# bekono_mini.net
KiCad netlist of a schematic drawn in EAGLE
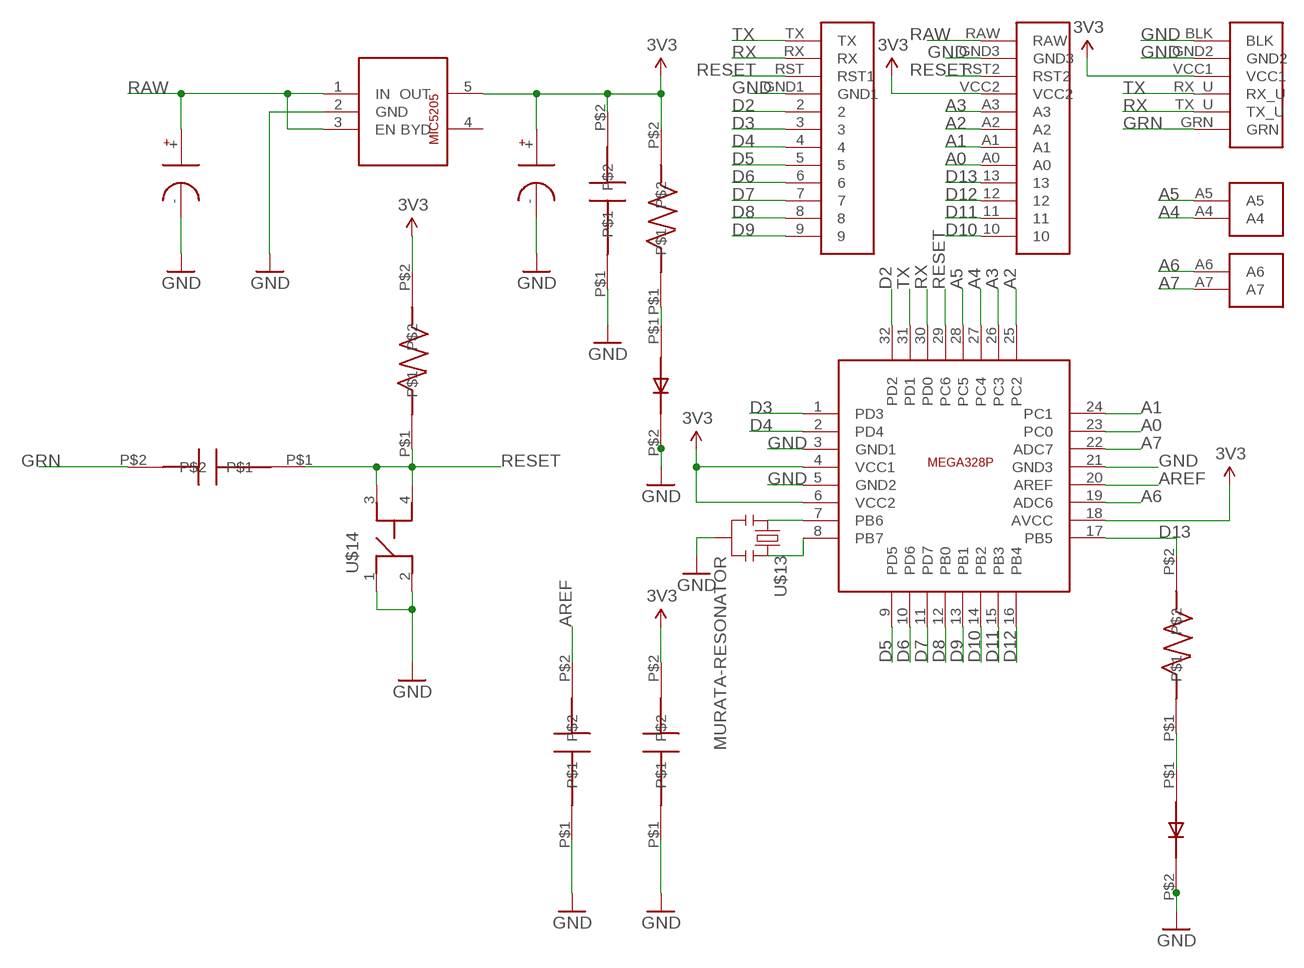
[diagram p0: schematic, sheet 1]

(export (version "E")
  (design (tool "Eeschema 10.0.6"))
  (components
    (comp (ref "U$1")
      (value "ARDUIN-MINIPRO-BASE")
      (footprint "eagle-import:ARDUINO-MINIPRO-BASE")
      (libsource (lib "eagle-import") (part "ARDUIN-MINIPRO-BASE"))
    )
    (comp (ref "U$2")
      (value "MICREL-MIC5205")
      (footprint "eagle-import:MICREL-MIC5205")
      (libsource (lib "eagle-import") (part "MICREL-MIC5205"))
    )
    (comp (ref "U$3")
      (value "TANTALUM-CAPACITOR-1206")
      (footprint "eagle-import:TANTALUM-CAPACITOR-1206")
      (libsource (lib "eagle-import") (part "TANTALUM-CAPACITOR-1206"))
    )
    (comp (ref "U$4")
      (value "TANTALUM-CAPACITOR-1206")
      (footprint "eagle-import:TANTALUM-CAPACITOR-1206")
      (libsource (lib "eagle-import") (part "TANTALUM-CAPACITOR-1206"))
    )
    (comp (ref "U$5")
      (value "CAPACITOR-0603")
      (footprint "eagle-import:0603")
      (libsource (lib "eagle-import") (part "CAPACITOR-0603"))
    )
    (comp (ref "U$6")
      (value "RESISTOR-0603")
      (footprint "eagle-import:0603")
      (libsource (lib "eagle-import") (part "RESISTOR-0603"))
    )
    (comp (ref "U$7")
      (value "LED-0603")
      (footprint "eagle-import:0603")
      (libsource (lib "eagle-import") (part "LED-0603"))
    )
    (comp (ref "U$8")
      (value "ATMEL-MEGA328P")
      (footprint "eagle-import:ATNEL-MEGA328P")
      (libsource (lib "eagle-import") (part "ATMEL-MEGA328P"))
    )
    (comp (ref "U$9")
      (value "RESISTOR-0603")
      (footprint "eagle-import:0603")
      (libsource (lib "eagle-import") (part "RESISTOR-0603"))
    )
    (comp (ref "U$10")
      (value "LED-0603")
      (footprint "eagle-import:0603")
      (libsource (lib "eagle-import") (part "LED-0603"))
    )
    (comp (ref "U$11")
      (value "CAPACITOR-0603")
      (footprint "eagle-import:0603")
      (libsource (lib "eagle-import") (part "CAPACITOR-0603"))
    )
    (comp (ref "U$12")
      (value "CAPACITOR-0603")
      (footprint "eagle-import:0603")
      (libsource (lib "eagle-import") (part "CAPACITOR-0603"))
    )
    (comp (ref "U$13")
      (value "MURATA-RESONATOR")
      (footprint "eagle-import:MURATA-RESONATOR")
      (libsource (lib "eagle-import") (part "MURATA-RESONATOR"))
    )
    (comp (ref "U$14")
      (value "SWITCH-LS6J2M-T")
      (footprint "eagle-import:SWITCH-LS6J2M-T")
      (libsource (lib "eagle-import") (part "SWITCH-LS6J2M-T"))
    )
    (comp (ref "U$15")
      (value "RESISTOR-0603")
      (footprint "eagle-import:0603")
      (libsource (lib "eagle-import") (part "RESISTOR-0603"))
    )
    (comp (ref "U$16")
      (value "CAPACITOR-0603")
      (footprint "eagle-import:0603")
      (libsource (lib "eagle-import") (part "CAPACITOR-0603"))
    )
  )
  (nets
    (net (code "1") (name "/A0") (class "Default")
      (node (ref "U$1") (pin "A0") (pinfunction "A0_A0") (pintype "bidirectional"))
      (node (ref "U$8") (pin "23") (pinfunction "PC0_23") (pintype "bidirectional"))
    )
    (net (code "2") (name "/A1") (class "Default")
      (node (ref "U$1") (pin "A1") (pinfunction "A1_A1") (pintype "bidirectional"))
      (node (ref "U$8") (pin "24") (pinfunction "PC1_24") (pintype "bidirectional"))
    )
    (net (code "3") (name "/A2") (class "Default")
      (node (ref "U$1") (pin "A2") (pinfunction "A2_A2") (pintype "bidirectional"))
      (node (ref "U$8") (pin "25") (pinfunction "PC2_25") (pintype "bidirectional"))
    )
    (net (code "4") (name "/A3") (class "Default")
      (node (ref "U$1") (pin "A3") (pinfunction "A3_A3") (pintype "bidirectional"))
      (node (ref "U$8") (pin "26") (pinfunction "PC3_26") (pintype "bidirectional"))
    )
    (net (code "5") (name "/A4") (class "Default")
      (node (ref "U$1") (pin "A4") (pinfunction "A4_A4") (pintype "bidirectional"))
      (node (ref "U$8") (pin "27") (pinfunction "PC4_27") (pintype "bidirectional"))
    )
    (net (code "6") (name "/A5") (class "Default")
      (node (ref "U$1") (pin "A5") (pinfunction "A5_A5") (pintype "bidirectional"))
      (node (ref "U$8") (pin "28") (pinfunction "PC5_28") (pintype "bidirectional"))
    )
    (net (code "7") (name "/A6") (class "Default")
      (node (ref "U$1") (pin "A6") (pinfunction "A6_A6") (pintype "bidirectional"))
      (node (ref "U$8") (pin "19") (pinfunction "ADC6_19") (pintype "bidirectional"))
    )
    (net (code "8") (name "/A7") (class "Default")
      (node (ref "U$1") (pin "A7") (pinfunction "A7_A7") (pintype "bidirectional"))
      (node (ref "U$8") (pin "22") (pinfunction "ADC7_22") (pintype "bidirectional"))
    )
    (net (code "9") (name "/AREF") (class "Default")
      (node (ref "U$12") (pin "P$2") (pinfunction "P$2_P$2") (pintype "bidirectional"))
      (node (ref "U$8") (pin "20") (pinfunction "AREF_20") (pintype "bidirectional"))
    )
    (net (code "10") (name "/D2") (class "Default")
      (node (ref "U$1") (pin "2") (pinfunction "2_2") (pintype "bidirectional"))
      (node (ref "U$8") (pin "32") (pinfunction "PD2_32") (pintype "bidirectional"))
    )
    (net (code "11") (name "/D3") (class "Default")
      (node (ref "U$1") (pin "3") (pinfunction "3_3") (pintype "bidirectional"))
      (node (ref "U$8") (pin "1") (pinfunction "PD3_1") (pintype "bidirectional"))
    )
    (net (code "12") (name "/D4") (class "Default")
      (node (ref "U$1") (pin "4") (pinfunction "4_4") (pintype "bidirectional"))
      (node (ref "U$8") (pin "2") (pinfunction "PD4_2") (pintype "bidirectional"))
    )
    (net (code "13") (name "/D5") (class "Default")
      (node (ref "U$1") (pin "5") (pinfunction "5_5") (pintype "bidirectional"))
      (node (ref "U$8") (pin "9") (pinfunction "PD5_9") (pintype "bidirectional"))
    )
    (net (code "14") (name "/D6") (class "Default")
      (node (ref "U$1") (pin "6") (pinfunction "6_6") (pintype "bidirectional"))
      (node (ref "U$8") (pin "10") (pinfunction "PD6_10") (pintype "bidirectional"))
    )
    (net (code "15") (name "/D7") (class "Default")
      (node (ref "U$1") (pin "7") (pinfunction "7_7") (pintype "bidirectional"))
      (node (ref "U$8") (pin "11") (pinfunction "PD7_11") (pintype "bidirectional"))
    )
    (net (code "16") (name "/D8") (class "Default")
      (node (ref "U$1") (pin "8") (pinfunction "8_8") (pintype "bidirectional"))
      (node (ref "U$8") (pin "12") (pinfunction "PB0_12") (pintype "bidirectional"))
    )
    (net (code "17") (name "/D9") (class "Default")
      (node (ref "U$1") (pin "9") (pinfunction "9_9") (pintype "bidirectional"))
      (node (ref "U$8") (pin "13") (pinfunction "PB1_13") (pintype "bidirectional"))
    )
    (net (code "18") (name "/D10") (class "Default")
      (node (ref "U$1") (pin "10") (pinfunction "10_10") (pintype "bidirectional"))
      (node (ref "U$8") (pin "14") (pinfunction "PB2_14") (pintype "bidirectional"))
    )
    (net (code "19") (name "/D11") (class "Default")
      (node (ref "U$1") (pin "11") (pinfunction "11_11") (pintype "bidirectional"))
      (node (ref "U$8") (pin "15") (pinfunction "PB3_15") (pintype "bidirectional"))
    )
    (net (code "20") (name "/D12") (class "Default")
      (node (ref "U$1") (pin "12") (pinfunction "12_12") (pintype "bidirectional"))
      (node (ref "U$8") (pin "16") (pinfunction "PB4_16") (pintype "bidirectional"))
    )
    (net (code "21") (name "/D13") (class "Default")
      (node (ref "U$1") (pin "13") (pinfunction "13_13") (pintype "bidirectional"))
      (node (ref "U$8") (pin "17") (pinfunction "PB5_17") (pintype "bidirectional"))
      (node (ref "U$9") (pin "P$2") (pinfunction "P$2_P$2") (pintype "bidirectional"))
    )
    (net (code "22") (name "/GRN") (class "Default")
      (node (ref "U$1") (pin "GRN") (pinfunction "GRN_GRN") (pintype "bidirectional"))
      (node (ref "U$16") (pin "P$2") (pinfunction "P$2_P$2") (pintype "bidirectional"))
    )
    (net (code "23") (name "/RAW") (class "Default")
      (node (ref "U$1") (pin "RAW") (pinfunction "RAW_RAW") (pintype "bidirectional"))
      (node (ref "U$2") (pin "1") (pinfunction "IN_1") (pintype "bidirectional"))
      (node (ref "U$2") (pin "3") (pinfunction "EN_3") (pintype "bidirectional"))
      (node (ref "U$3") (pin "+") (pinfunction "+_+") (pintype "bidirectional"))
    )
    (net (code "24") (name "/RESET") (class "Default")
      (node (ref "U$1") (pin "RST") (pinfunction "RST1_RST") (pintype "bidirectional"))
      (node (ref "U$1") (pin "RST2") (pinfunction "RST2_RST2") (pintype "bidirectional"))
      (node (ref "U$14") (pin "3") (pinfunction "3_3") (pintype "bidirectional"))
      (node (ref "U$14") (pin "4") (pinfunction "4_4") (pintype "bidirectional"))
      (node (ref "U$15") (pin "P$1") (pinfunction "P$1_P$1") (pintype "bidirectional"))
      (node (ref "U$16") (pin "P$1") (pinfunction "P$1_P$1") (pintype "bidirectional"))
      (node (ref "U$8") (pin "29") (pinfunction "PC6_29") (pintype "bidirectional"))
    )
    (net (code "25") (name "/RX") (class "Default")
      (node (ref "U$1") (pin "RX") (pinfunction "RX_RX") (pintype "bidirectional"))
      (node (ref "U$1") (pin "TX_U") (pinfunction "TX_U_TX_U") (pintype "bidirectional"))
      (node (ref "U$8") (pin "30") (pinfunction "PD0_30") (pintype "bidirectional"))
    )
    (net (code "26") (name "/TX") (class "Default")
      (node (ref "U$1") (pin "RX_U") (pinfunction "RX_U_RX_U") (pintype "bidirectional"))
      (node (ref "U$1") (pin "TX") (pinfunction "TX_TX") (pintype "bidirectional"))
      (node (ref "U$8") (pin "31") (pinfunction "PD1_31") (pintype "bidirectional"))
    )
    (net (code "27") (name "3V3") (class "Default")
      (node (ref "U$1") (pin "VCC1") (pinfunction "VCC1_VCC1") (pintype "bidirectional"))
      (node (ref "U$1") (pin "VCC2") (pinfunction "VCC2_VCC2") (pintype "bidirectional"))
      (node (ref "U$11") (pin "P$2") (pinfunction "P$2_P$2") (pintype "bidirectional"))
      (node (ref "U$15") (pin "P$2") (pinfunction "P$2_P$2") (pintype "bidirectional"))
      (node (ref "U$2") (pin "5") (pinfunction "OUT_5") (pintype "bidirectional"))
      (node (ref "U$4") (pin "+") (pinfunction "+_+") (pintype "bidirectional"))
      (node (ref "U$5") (pin "P$2") (pinfunction "P$2_P$2") (pintype "bidirectional"))
      (node (ref "U$6") (pin "P$2") (pinfunction "P$2_P$2") (pintype "bidirectional"))
      (node (ref "U$8") (pin "18") (pinfunction "AVCC_18") (pintype "bidirectional"))
      (node (ref "U$8") (pin "4") (pinfunction "VCC1_4") (pintype "bidirectional"))
      (node (ref "U$8") (pin "6") (pinfunction "VCC2_6") (pintype "bidirectional"))
    )
    (net (code "28") (name "GND") (class "Default")
      (node (ref "U$1") (pin "BLK") (pinfunction "BLK_BLK") (pintype "bidirectional"))
      (node (ref "U$1") (pin "GND1") (pinfunction "GND1_GND1") (pintype "bidirectional"))
      (node (ref "U$1") (pin "GND2") (pinfunction "GND2_GND2") (pintype "bidirectional"))
      (node (ref "U$1") (pin "GND3") (pinfunction "GND3_GND3") (pintype "bidirectional"))
      (node (ref "U$10") (pin "P$2") (pinfunction "P$2_P$2") (pintype "bidirectional"))
      (node (ref "U$11") (pin "P$1") (pinfunction "P$1_P$1") (pintype "bidirectional"))
      (node (ref "U$12") (pin "P$1") (pinfunction "P$1_P$1") (pintype "bidirectional"))
      (node (ref "U$13") (pin "2") (pinfunction "2_2") (pintype "passive"))
      (node (ref "U$14") (pin "1") (pinfunction "1_1") (pintype "bidirectional"))
      (node (ref "U$14") (pin "2") (pinfunction "2_2") (pintype "bidirectional"))
      (node (ref "U$2") (pin "2") (pinfunction "GND_2") (pintype "bidirectional"))
      (node (ref "U$3") (pin "-") (pinfunction "-_-") (pintype "bidirectional"))
      (node (ref "U$4") (pin "-") (pinfunction "-_-") (pintype "bidirectional"))
      (node (ref "U$5") (pin "P$1") (pinfunction "P$1_P$1") (pintype "bidirectional"))
      (node (ref "U$7") (pin "P$2") (pinfunction "P$2_P$2") (pintype "bidirectional"))
      (node (ref "U$8") (pin "21") (pinfunction "GND3_21") (pintype "bidirectional"))
      (node (ref "U$8") (pin "3") (pinfunction "GND1_3") (pintype "bidirectional"))
      (node (ref "U$8") (pin "5") (pinfunction "GND2_5") (pintype "bidirectional"))
    )
    (net (code "29") (name "Net-(U$6-PadP$1)") (class "Default")
      (node (ref "U$6") (pin "P$1") (pinfunction "P$1_P$1") (pintype "bidirectional"))
      (node (ref "U$7") (pin "P$1") (pinfunction "P$1_P$1") (pintype "bidirectional"))
    )
    (net (code "30") (name "Net-(U$8-PB6)") (class "Default")
      (node (ref "U$13") (pin "1") (pinfunction "1_1") (pintype "passive"))
      (node (ref "U$8") (pin "7") (pinfunction "PB6_7") (pintype "bidirectional"))
    )
    (net (code "31") (name "Net-(U$8-PB7)") (class "Default")
      (node (ref "U$13") (pin "3") (pinfunction "3_3") (pintype "passive"))
      (node (ref "U$8") (pin "8") (pinfunction "PB7_8") (pintype "bidirectional"))
    )
    (net (code "32") (name "Net-(U$10-PadP$1)") (class "Default")
      (node (ref "U$10") (pin "P$1") (pinfunction "P$1_P$1") (pintype "bidirectional"))
      (node (ref "U$9") (pin "P$1") (pinfunction "P$1_P$1") (pintype "bidirectional"))
    )
    (net (code "33") (name "unconnected-(U$2-BYD-Pad4)") (class "Default")
      (node (ref "U$2") (pin "4") (pinfunction "BYD_4") (pintype "bidirectional"))
    )
  )
)
